# Arduino_MEGA_blank_shield.net
KiCad netlist of a schematic drawn in EAGLE
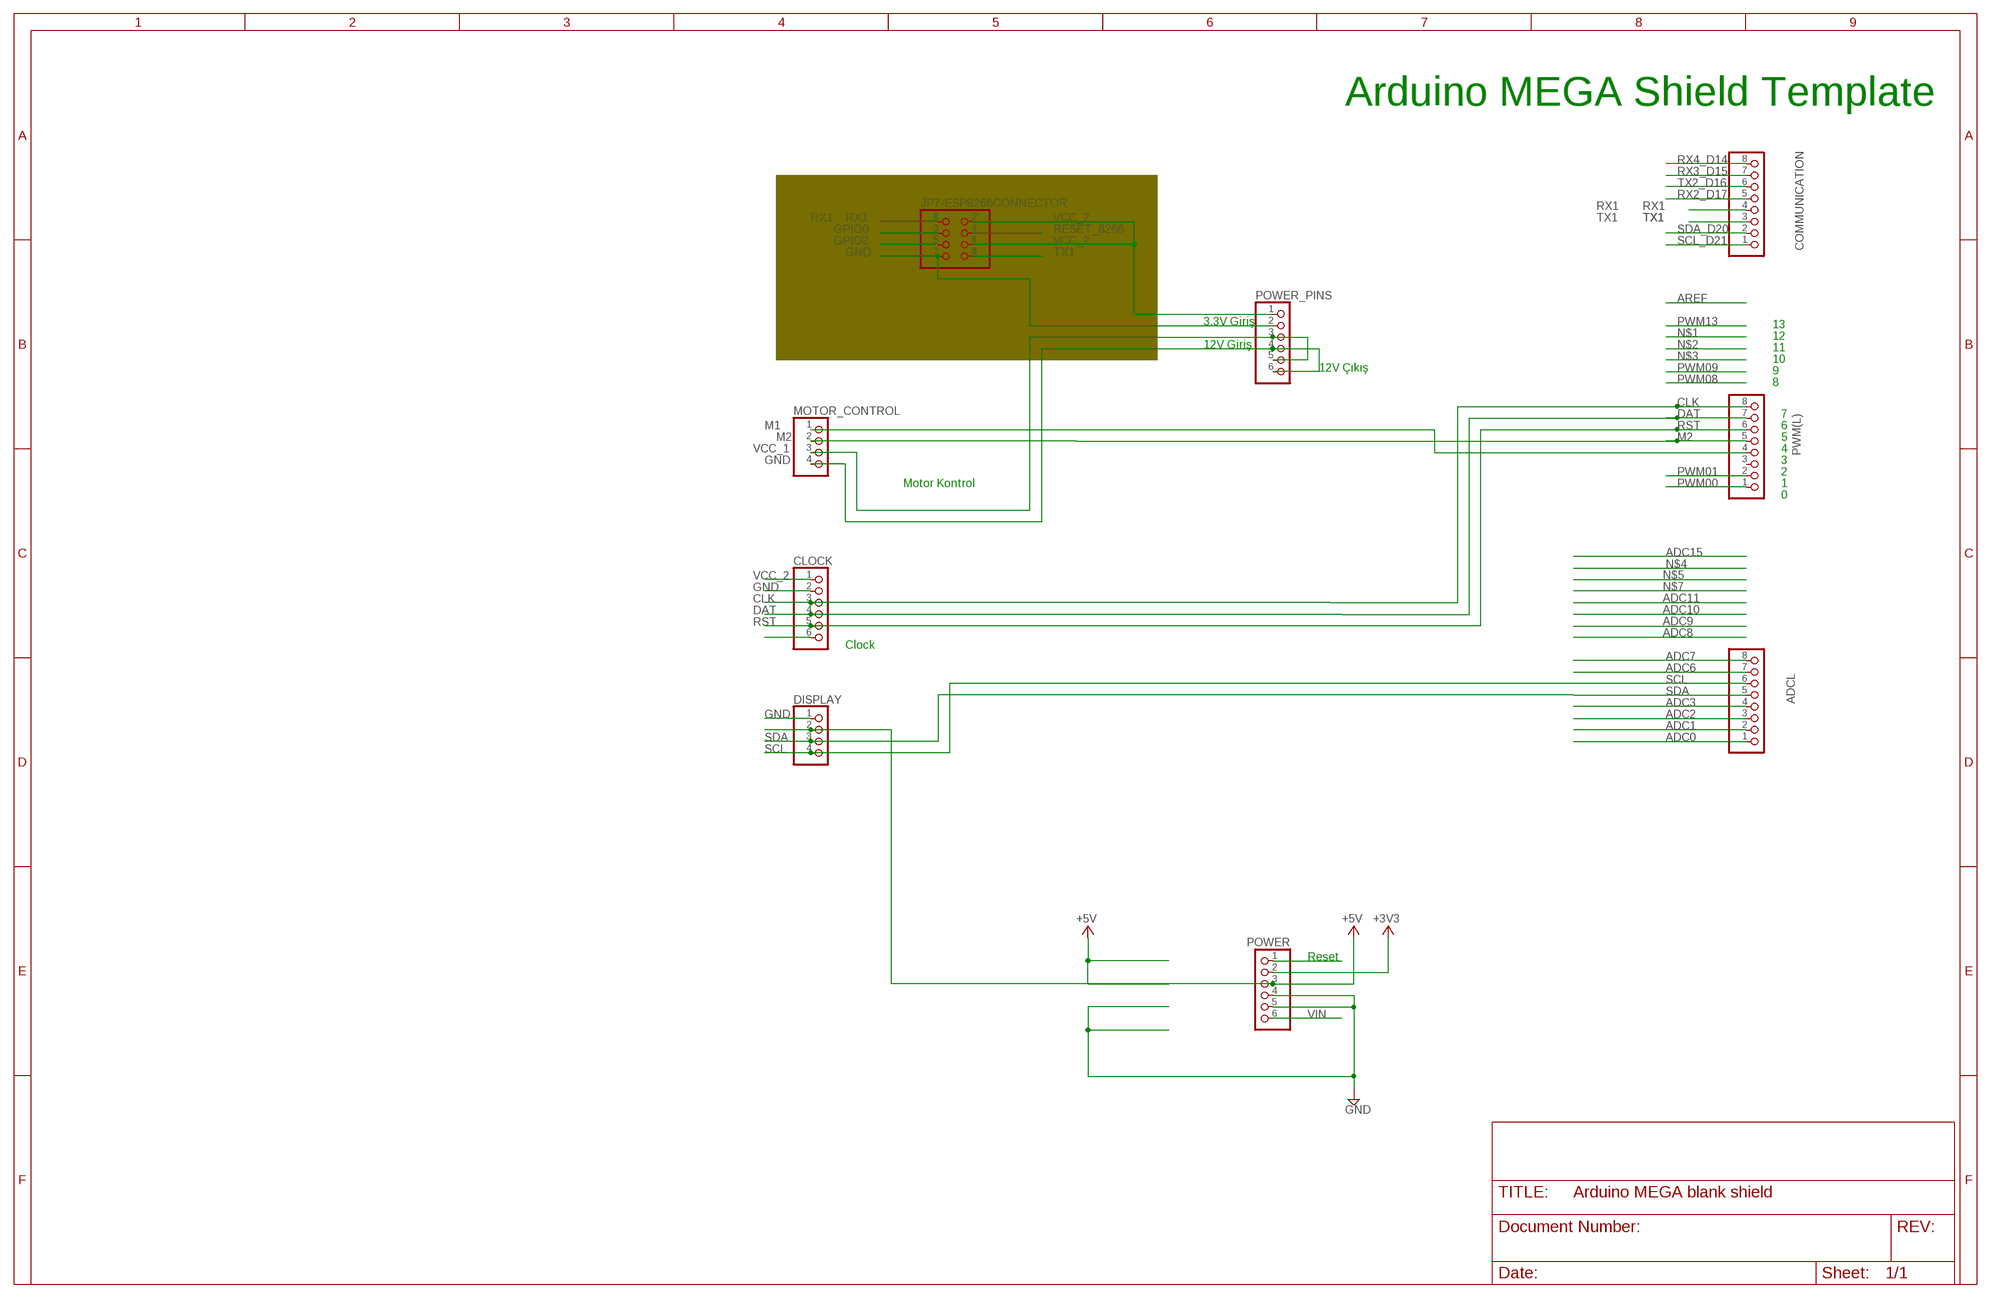
[diagram p0: schematic, sheet 1]

(export (version "E")
  (design (tool "Eeschema 10.0.6"))
  (components
    (comp (ref "ADCL")
      (value "PINHD-1X8")
      (footprint "eagle-import:1X08")
      (libsource (lib "eagle-import") (part "PINHD-1X8"))
    )
    (comp (ref "CLOCK")
      (value "PINHD-1X6")
      (footprint "eagle-import:1X06")
      (libsource (lib "eagle-import") (part "PINHD-1X6"))
    )
    (comp (ref "COMMUNICATION")
      (value "PINHD-1X8")
      (footprint "eagle-import:1X08")
      (libsource (lib "eagle-import") (part "PINHD-1X8"))
    )
    (comp (ref "DISPLAY")
      (value "PINHD-1X4")
      (footprint "eagle-import:1X04")
      (libsource (lib "eagle-import") (part "PINHD-1X4"))
    )
    (comp (ref "JP7-ESP8266CONNECTOR")
      (value "PINHD-2X4")
      (footprint "eagle-import:2X04")
      (libsource (lib "eagle-import") (part "PINHD-2X4"))
    )
    (comp (ref "MOTOR_CONTROL")
      (value "PINHD-1X4")
      (footprint "eagle-import:1X04")
      (fields (field (name "SPICEPREFIX") "E"))
      (libsource (lib "eagle-import") (part "PINHD-1X4"))
    )
    (comp (ref "POWER")
      (value "PINHD-1X6")
      (footprint "eagle-import:1X06")
      (libsource (lib "eagle-import") (part "PINHD-1X6"))
    )
    (comp (ref "POWER_PINS")
      (value "PINHD-1X6")
      (footprint "eagle-import:1X06")
      (libsource (lib "eagle-import") (part "PINHD-1X6"))
    )
    (comp (ref "PWM(L)")
      (value "PINHD-1X8")
      (footprint "eagle-import:1X08")
      (libsource (lib "eagle-import") (part "PINHD-1X8"))
    )
  )
  (nets
    (net (code "1") (name "+3V3") (class "Default")
      (node (ref "POWER") (pin "2") (pinfunction "2_2") (pintype "passive"))
    )
    (net (code "2") (name "+5V") (class "Default")
      (node (ref "DISPLAY") (pin "2") (pinfunction "2_2") (pintype "passive"))
      (node (ref "POWER") (pin "3") (pinfunction "3_3") (pintype "passive"))
    )
    (net (code "3") (name "/ADC0") (class "Default")
      (node (ref "ADCL") (pin "1") (pinfunction "1_1") (pintype "passive"))
    )
    (net (code "4") (name "/ADC1") (class "Default")
      (node (ref "ADCL") (pin "2") (pinfunction "2_2") (pintype "passive"))
    )
    (net (code "5") (name "/ADC2") (class "Default")
      (node (ref "ADCL") (pin "3") (pinfunction "3_3") (pintype "passive"))
    )
    (net (code "6") (name "/ADC3") (class "Default")
      (node (ref "ADCL") (pin "4") (pinfunction "4_4") (pintype "passive"))
    )
    (net (code "7") (name "/ADC6") (class "Default")
      (node (ref "ADCL") (pin "7") (pinfunction "7_7") (pintype "passive"))
    )
    (net (code "8") (name "/ADC7") (class "Default")
      (node (ref "ADCL") (pin "8") (pinfunction "8_8") (pintype "passive"))
    )
    (net (code "15") (name "/CLK") (class "Default")
      (node (ref "CLOCK") (pin "3") (pinfunction "3_3") (pintype "passive"))
      (node (ref "PWM(L)") (pin "8") (pinfunction "8_8") (pintype "passive"))
    )
    (net (code "16") (name "/DAT") (class "Default")
      (node (ref "CLOCK") (pin "4") (pinfunction "4_4") (pintype "passive"))
      (node (ref "PWM(L)") (pin "7") (pinfunction "7_7") (pintype "passive"))
    )
    (net (code "17") (name "/GPIO0") (class "Default")
      (node (ref "JP7-ESP8266CONNECTOR") (pin "3") (pinfunction "3_3") (pintype "passive"))
    )
    (net (code "18") (name "/GPIO2") (class "Default")
      (node (ref "JP7-ESP8266CONNECTOR") (pin "5") (pinfunction "5_5") (pintype "passive"))
    )
    (net (code "19") (name "/M1") (class "Default")
      (node (ref "MOTOR_CONTROL") (pin "1") (pinfunction "1_1") (pintype "passive"))
      (node (ref "PWM(L)") (pin "4") (pinfunction "4_4") (pintype "passive"))
    )
    (net (code "20") (name "/M2") (class "Default")
      (node (ref "MOTOR_CONTROL") (pin "2") (pinfunction "2_2") (pintype "passive"))
      (node (ref "PWM(L)") (pin "5") (pinfunction "5_5") (pintype "passive"))
    )
    (net (code "27") (name "/PWM00") (class "Default")
      (node (ref "PWM(L)") (pin "1") (pinfunction "1_1") (pintype "passive"))
    )
    (net (code "28") (name "/PWM01") (class "Default")
      (node (ref "PWM(L)") (pin "2") (pinfunction "2_2") (pintype "passive"))
    )
    (net (code "32") (name "/RESET_8266") (class "Default")
      (node (ref "JP7-ESP8266CONNECTOR") (pin "4") (pinfunction "4_4") (pintype "passive"))
    )
    (net (code "33") (name "/RST") (class "Default")
      (node (ref "CLOCK") (pin "5") (pinfunction "5_5") (pintype "passive"))
      (node (ref "PWM(L)") (pin "6") (pinfunction "6_6") (pintype "passive"))
    )
    (net (code "34") (name "/RX1") (class "Default")
      (node (ref "COMMUNICATION") (pin "4") (pinfunction "4_4") (pintype "passive"))
      (node (ref "JP7-ESP8266CONNECTOR") (pin "1") (pinfunction "1_1") (pintype "passive"))
    )
    (net (code "35") (name "/RX2_D17") (class "Default")
      (node (ref "COMMUNICATION") (pin "5") (pinfunction "5_5") (pintype "passive"))
    )
    (net (code "36") (name "/RX3_D15") (class "Default")
      (node (ref "COMMUNICATION") (pin "7") (pinfunction "7_7") (pintype "passive"))
    )
    (net (code "37") (name "/RX4_D14") (class "Default")
      (node (ref "COMMUNICATION") (pin "8") (pinfunction "8_8") (pintype "passive"))
    )
    (net (code "38") (name "/SCL") (class "Default")
      (node (ref "ADCL") (pin "6") (pinfunction "6_6") (pintype "passive"))
      (node (ref "DISPLAY") (pin "4") (pinfunction "GND_4") (pintype "passive"))
    )
    (net (code "39") (name "/SCL_D21") (class "Default")
      (node (ref "COMMUNICATION") (pin "1") (pinfunction "1_1") (pintype "passive"))
    )
    (net (code "40") (name "/SDA") (class "Default")
      (node (ref "ADCL") (pin "5") (pinfunction "5_5") (pintype "passive"))
      (node (ref "DISPLAY") (pin "3") (pinfunction "3_3") (pintype "passive"))
    )
    (net (code "41") (name "/SDA_D20") (class "Default")
      (node (ref "COMMUNICATION") (pin "2") (pinfunction "2_2") (pintype "passive"))
    )
    (net (code "42") (name "/TX1") (class "Default")
      (node (ref "COMMUNICATION") (pin "3") (pinfunction "3_3") (pintype "passive"))
      (node (ref "JP7-ESP8266CONNECTOR") (pin "8") (pinfunction "8_8") (pintype "passive"))
    )
    (net (code "43") (name "/TX2_D16") (class "Default")
      (node (ref "COMMUNICATION") (pin "6") (pinfunction "6_6") (pintype "passive"))
    )
    (net (code "44") (name "/VCC_1") (class "Default")
      (node (ref "MOTOR_CONTROL") (pin "3") (pinfunction "3_3") (pintype "passive"))
      (node (ref "POWER_PINS") (pin "3") (pinfunction "3_3") (pintype "passive"))
      (node (ref "POWER_PINS") (pin "5") (pinfunction "5_5") (pintype "passive"))
    )
    (net (code "45") (name "/VCC_2") (class "Default")
      (node (ref "CLOCK") (pin "1") (pinfunction "1_1") (pintype "passive"))
      (node (ref "JP7-ESP8266CONNECTOR") (pin "2") (pinfunction "2_2") (pintype "passive"))
      (node (ref "JP7-ESP8266CONNECTOR") (pin "6") (pinfunction "6_6") (pintype "passive"))
      (node (ref "POWER_PINS") (pin "1") (pinfunction "1_1") (pintype "passive"))
    )
    (net (code "46") (name "/VIN") (class "Default")
      (node (ref "POWER") (pin "6") (pinfunction "6_6") (pintype "passive"))
    )
    (net (code "47") (name "GND") (class "Default")
      (node (ref "CLOCK") (pin "2") (pinfunction "2_2") (pintype "passive"))
      (node (ref "DISPLAY") (pin "1") (pinfunction "1_1") (pintype "passive"))
      (node (ref "JP7-ESP8266CONNECTOR") (pin "7") (pinfunction "7_7") (pintype "passive"))
      (node (ref "MOTOR_CONTROL") (pin "4") (pinfunction "GND_4") (pintype "passive"))
      (node (ref "POWER") (pin "4") (pinfunction "4_4") (pintype "passive"))
      (node (ref "POWER") (pin "5") (pinfunction "5_5") (pintype "passive"))
      (node (ref "POWER_PINS") (pin "2") (pinfunction "2_2") (pintype "passive"))
      (node (ref "POWER_PINS") (pin "4") (pinfunction "4_4") (pintype "passive"))
      (node (ref "POWER_PINS") (pin "6") (pinfunction "6_6") (pintype "passive"))
    )
    (net (code "48") (name "unconnected-(CLOCK-Pad6)") (class "Default")
      (node (ref "CLOCK") (pin "6") (pinfunction "6_6") (pintype "passive"))
    )
    (net (code "49") (name "unconnected-(POWER-Pad1)") (class "Default")
      (node (ref "POWER") (pin "1") (pinfunction "1_1") (pintype "passive"))
    )
    (net (code "50") (name "unconnected-(PWM(L)-Pad3)") (class "Default")
      (node (ref "PWM(L)") (pin "3") (pinfunction "3_3") (pintype "passive"))
    )
  )
)
